# AtlasShield.net
KiCad netlist of a schematic drawn in EAGLE
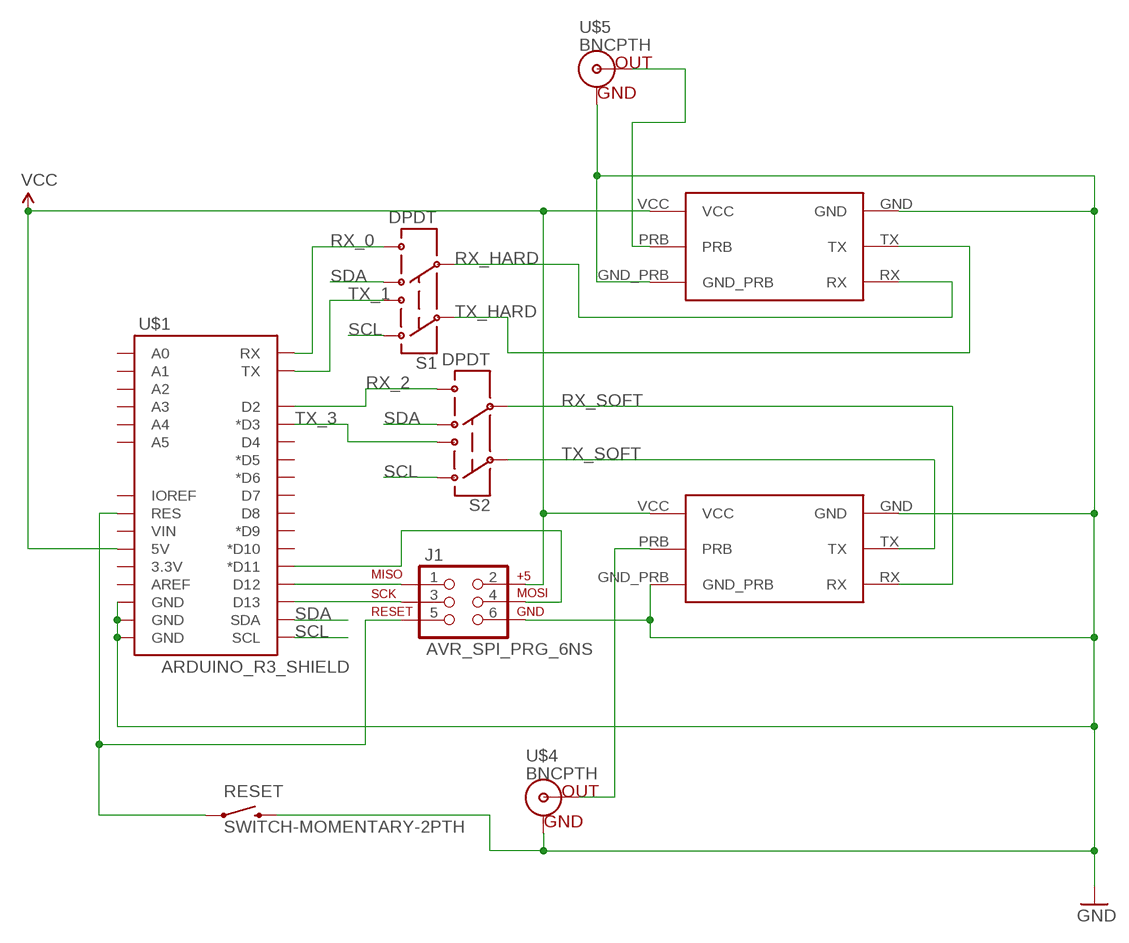
[diagram p0: schematic, sheet 1]

(export (version "E")
  (design (tool "Eeschema 10.0.6"))
  (components
    (comp (ref "J1")
      (value "AVR_SPI_PRG_6NS")
      (footprint "eagle-import:2X3-NS")
      (libsource (lib "eagle-import") (part "AVR_SPI_PRG_6NS"))
    )
    (comp (ref "RESET")
      (value "SWITCH-MOMENTARY-2PTH")
      (footprint "eagle-import:TACTILE-PTH")
      (libsource (lib "eagle-import") (part "SWITCH-MOMENTARY-2PTH"))
    )
    (comp (ref "S1")
      (value "DPDT")
      (footprint "eagle-import:AYZ0202")
      (libsource (lib "eagle-import") (part "SWITCH-DPDTAYZ0202"))
    )
    (comp (ref "S2")
      (value "DPDT")
      (footprint "eagle-import:AYZ0202")
      (libsource (lib "eagle-import") (part "SWITCH-DPDTAYZ0202"))
    )
    (comp (ref "U$1")
      (value "ARDUINO_R3_SHIELD")
      (footprint "eagle-import:UNO_R3_SHIELD")
      (libsource (lib "eagle-import") (part "ARDUINO_R3_SHIELD"))
    )
    (comp (ref "U$2")
      (value "ATLAS-CIRCUIT")
      (footprint "eagle-import:ATLAS-CIRCUIT")
      (libsource (lib "eagle-import") (part "ATLAS-CIRCUIT"))
    )
    (comp (ref "U$3")
      (value "ATLAS-CIRCUIT")
      (footprint "eagle-import:ATLAS-CIRCUIT")
      (libsource (lib "eagle-import") (part "ATLAS-CIRCUIT"))
    )
    (comp (ref "U$4")
      (value "BNCPTH")
      (footprint "eagle-import:BNC")
      (libsource (lib "eagle-import") (part "BNCPTH"))
    )
    (comp (ref "U$5")
      (value "BNCPTH")
      (footprint "eagle-import:BNC")
      (libsource (lib "eagle-import") (part "BNCPTH"))
    )
  )
  (nets
    (net (code "1") (name "/RX_0") (class "Default")
      (node (ref "S1") (pin "6") (pinfunction "6_6") (pintype "bidirectional"))
      (node (ref "U$1") (pin "RX") (pinfunction "RX_RX") (pintype "bidirectional"))
    )
    (net (code "2") (name "/RX_2") (class "Default")
      (node (ref "S2") (pin "6") (pinfunction "6_6") (pintype "bidirectional"))
      (node (ref "U$1") (pin "D2") (pinfunction "D2_D2") (pintype "bidirectional"))
    )
    (net (code "3") (name "/RX_HARD") (class "Default")
      (node (ref "S1") (pin "5") (pinfunction "5_5") (pintype "bidirectional"))
      (node (ref "U$2") (pin "RX") (pinfunction "RX_RX") (pintype "bidirectional"))
    )
    (net (code "4") (name "/RX_SOFT") (class "Default")
      (node (ref "S2") (pin "5") (pinfunction "5_5") (pintype "bidirectional"))
      (node (ref "U$3") (pin "RX") (pinfunction "RX_RX") (pintype "bidirectional"))
    )
    (net (code "5") (name "/SCL") (class "Default")
      (node (ref "S1") (pin "1") (pinfunction "1_1") (pintype "bidirectional"))
      (node (ref "S2") (pin "1") (pinfunction "1_1") (pintype "bidirectional"))
      (node (ref "U$1") (pin "SCL") (pinfunction "SCL_SCL") (pintype "bidirectional"))
    )
    (net (code "6") (name "/SDA") (class "Default")
      (node (ref "S1") (pin "4") (pinfunction "4_4") (pintype "bidirectional"))
      (node (ref "S2") (pin "4") (pinfunction "4_4") (pintype "bidirectional"))
      (node (ref "U$1") (pin "SDA") (pinfunction "SDA_SDA") (pintype "bidirectional"))
    )
    (net (code "7") (name "/TX_1") (class "Default")
      (node (ref "S1") (pin "3") (pinfunction "3_3") (pintype "bidirectional"))
      (node (ref "U$1") (pin "TX") (pinfunction "TX_TX") (pintype "bidirectional"))
    )
    (net (code "8") (name "/TX_3") (class "Default")
      (node (ref "S2") (pin "3") (pinfunction "3_3") (pintype "bidirectional"))
      (node (ref "U$1") (pin "D3") (pinfunction "*D3_D3") (pintype "bidirectional"))
    )
    (net (code "9") (name "/TX_HARD") (class "Default")
      (node (ref "S1") (pin "2") (pinfunction "2_2") (pintype "bidirectional"))
      (node (ref "U$2") (pin "TX") (pinfunction "TX_TX") (pintype "bidirectional"))
    )
    (net (code "10") (name "/TX_SOFT") (class "Default")
      (node (ref "S2") (pin "2") (pinfunction "2_2") (pintype "bidirectional"))
      (node (ref "U$3") (pin "TX") (pinfunction "TX_TX") (pintype "bidirectional"))
    )
    (net (code "11") (name "GND") (class "Default")
      (node (ref "J1") (pin "6") (pinfunction "6_6") (pintype "passive"))
      (node (ref "RESET") (pin "3") (pinfunction "2_3") (pintype "passive"))
      (node (ref "U$1") (pin "GND@0") (pinfunction "GND_GND@0") (pintype "bidirectional"))
      (node (ref "U$1") (pin "GND@1") (pinfunction "GND_GND@1") (pintype "bidirectional"))
      (node (ref "U$1") (pin "GND@2") (pinfunction "GND_GND@2") (pintype "bidirectional"))
      (node (ref "U$2") (pin "GND") (pinfunction "GND_GND") (pintype "bidirectional"))
      (node (ref "U$2") (pin "GND_PRB") (pinfunction "GND_PRB_GND_PRB") (pintype "bidirectional"))
      (node (ref "U$3") (pin "GND") (pinfunction "GND_GND") (pintype "bidirectional"))
      (node (ref "U$3") (pin "GND_PRB") (pinfunction "GND_PRB_GND_PRB") (pintype "bidirectional"))
      (node (ref "U$4") (pin "GND") (pinfunction "GND_GND") (pintype "bidirectional"))
      (node (ref "U$5") (pin "GND") (pinfunction "GND_GND") (pintype "bidirectional"))
    )
    (net (code "12") (name "Net-(J1-Pad1)") (class "Default")
      (node (ref "J1") (pin "1") (pinfunction "1_1") (pintype "passive"))
      (node (ref "U$1") (pin "D12") (pinfunction "D12_D12") (pintype "bidirectional"))
    )
    (net (code "13") (name "Net-(J1-Pad3)") (class "Default")
      (node (ref "J1") (pin "3") (pinfunction "3_3") (pintype "passive"))
      (node (ref "U$1") (pin "D13") (pinfunction "D13_D13") (pintype "bidirectional"))
    )
    (net (code "14") (name "Net-(J1-Pad5)") (class "Default")
      (node (ref "J1") (pin "5") (pinfunction "5_5") (pintype "passive"))
      (node (ref "RESET") (pin "1") (pinfunction "1_1") (pintype "passive"))
      (node (ref "U$1") (pin "RES") (pinfunction "RES_RES") (pintype "bidirectional"))
    )
    (net (code "15") (name "Net-(U$1-*D11)") (class "Default")
      (node (ref "J1") (pin "4") (pinfunction "4_4") (pintype "passive"))
      (node (ref "U$1") (pin "D11") (pinfunction "*D11_D11") (pintype "bidirectional"))
    )
    (net (code "16") (name "Net-(U$4-OUT)") (class "Default")
      (node (ref "U$3") (pin "PRB") (pinfunction "PRB_PRB") (pintype "bidirectional"))
      (node (ref "U$4") (pin "S") (pinfunction "OUT_S") (pintype "bidirectional"))
    )
    (net (code "17") (name "Net-(U$5-OUT)") (class "Default")
      (node (ref "U$2") (pin "PRB") (pinfunction "PRB_PRB") (pintype "bidirectional"))
      (node (ref "U$5") (pin "S") (pinfunction "OUT_S") (pintype "bidirectional"))
    )
    (net (code "18") (name "VCC") (class "Default")
      (node (ref "J1") (pin "2") (pinfunction "2_2") (pintype "passive"))
      (node (ref "U$1") (pin "5V") (pinfunction "5V_5V") (pintype "bidirectional"))
      (node (ref "U$2") (pin "VCC") (pinfunction "VCC_VCC") (pintype "bidirectional"))
      (node (ref "U$3") (pin "VCC") (pinfunction "VCC_VCC") (pintype "bidirectional"))
    )
    (net (code "19") (name "unconnected-(U$1-*D5-PadD5)") (class "Default")
      (node (ref "U$1") (pin "D5") (pinfunction "*D5_D5") (pintype "bidirectional"))
    )
    (net (code "20") (name "unconnected-(U$1-*D6-PadD6)") (class "Default")
      (node (ref "U$1") (pin "D6") (pinfunction "*D6_D6") (pintype "bidirectional"))
    )
    (net (code "21") (name "unconnected-(U$1-*D9-PadD9)") (class "Default")
      (node (ref "U$1") (pin "D9") (pinfunction "*D9_D9") (pintype "bidirectional"))
    )
    (net (code "22") (name "unconnected-(U$1-*D10-PadD10)") (class "Default")
      (node (ref "U$1") (pin "D10") (pinfunction "*D10_D10") (pintype "bidirectional"))
    )
    (net (code "23") (name "unconnected-(U$1-Pad3.3V)") (class "Default")
      (node (ref "U$1") (pin "3.3V") (pinfunction "3.3V_3.3V") (pintype "bidirectional"))
    )
    (net (code "24") (name "unconnected-(U$1-PadA0)") (class "Default")
      (node (ref "U$1") (pin "A0") (pinfunction "A0_A0") (pintype "bidirectional"))
    )
    (net (code "25") (name "unconnected-(U$1-PadA1)") (class "Default")
      (node (ref "U$1") (pin "A1") (pinfunction "A1_A1") (pintype "bidirectional"))
    )
    (net (code "26") (name "unconnected-(U$1-PadA2)") (class "Default")
      (node (ref "U$1") (pin "A2") (pinfunction "A2_A2") (pintype "bidirectional"))
    )
    (net (code "27") (name "unconnected-(U$1-PadA3)") (class "Default")
      (node (ref "U$1") (pin "A3") (pinfunction "A3_A3") (pintype "bidirectional"))
    )
    (net (code "28") (name "unconnected-(U$1-PadA4)") (class "Default")
      (node (ref "U$1") (pin "A4") (pinfunction "A4_A4") (pintype "bidirectional"))
    )
    (net (code "29") (name "unconnected-(U$1-PadA5)") (class "Default")
      (node (ref "U$1") (pin "A5") (pinfunction "A5_A5") (pintype "bidirectional"))
    )
    (net (code "30") (name "unconnected-(U$1-PadAREF)") (class "Default")
      (node (ref "U$1") (pin "AREF") (pinfunction "AREF_AREF") (pintype "bidirectional"))
    )
    (net (code "31") (name "unconnected-(U$1-PadD4)") (class "Default")
      (node (ref "U$1") (pin "D4") (pinfunction "D4_D4") (pintype "bidirectional"))
    )
    (net (code "32") (name "unconnected-(U$1-PadD7)") (class "Default")
      (node (ref "U$1") (pin "D7") (pinfunction "D7_D7") (pintype "bidirectional"))
    )
    (net (code "33") (name "unconnected-(U$1-PadD8)") (class "Default")
      (node (ref "U$1") (pin "D8") (pinfunction "D8_D8") (pintype "bidirectional"))
    )
    (net (code "34") (name "unconnected-(U$1-PadIOREF)") (class "Default")
      (node (ref "U$1") (pin "IOREF") (pinfunction "IOREF_IOREF") (pintype "bidirectional"))
    )
    (net (code "35") (name "unconnected-(U$1-PadVIN)") (class "Default")
      (node (ref "U$1") (pin "VIN") (pinfunction "VIN_VIN") (pintype "bidirectional"))
    )
  )
)
